# TopLevel.net
KiCad netlist of a schematic drawn in Altium Designer
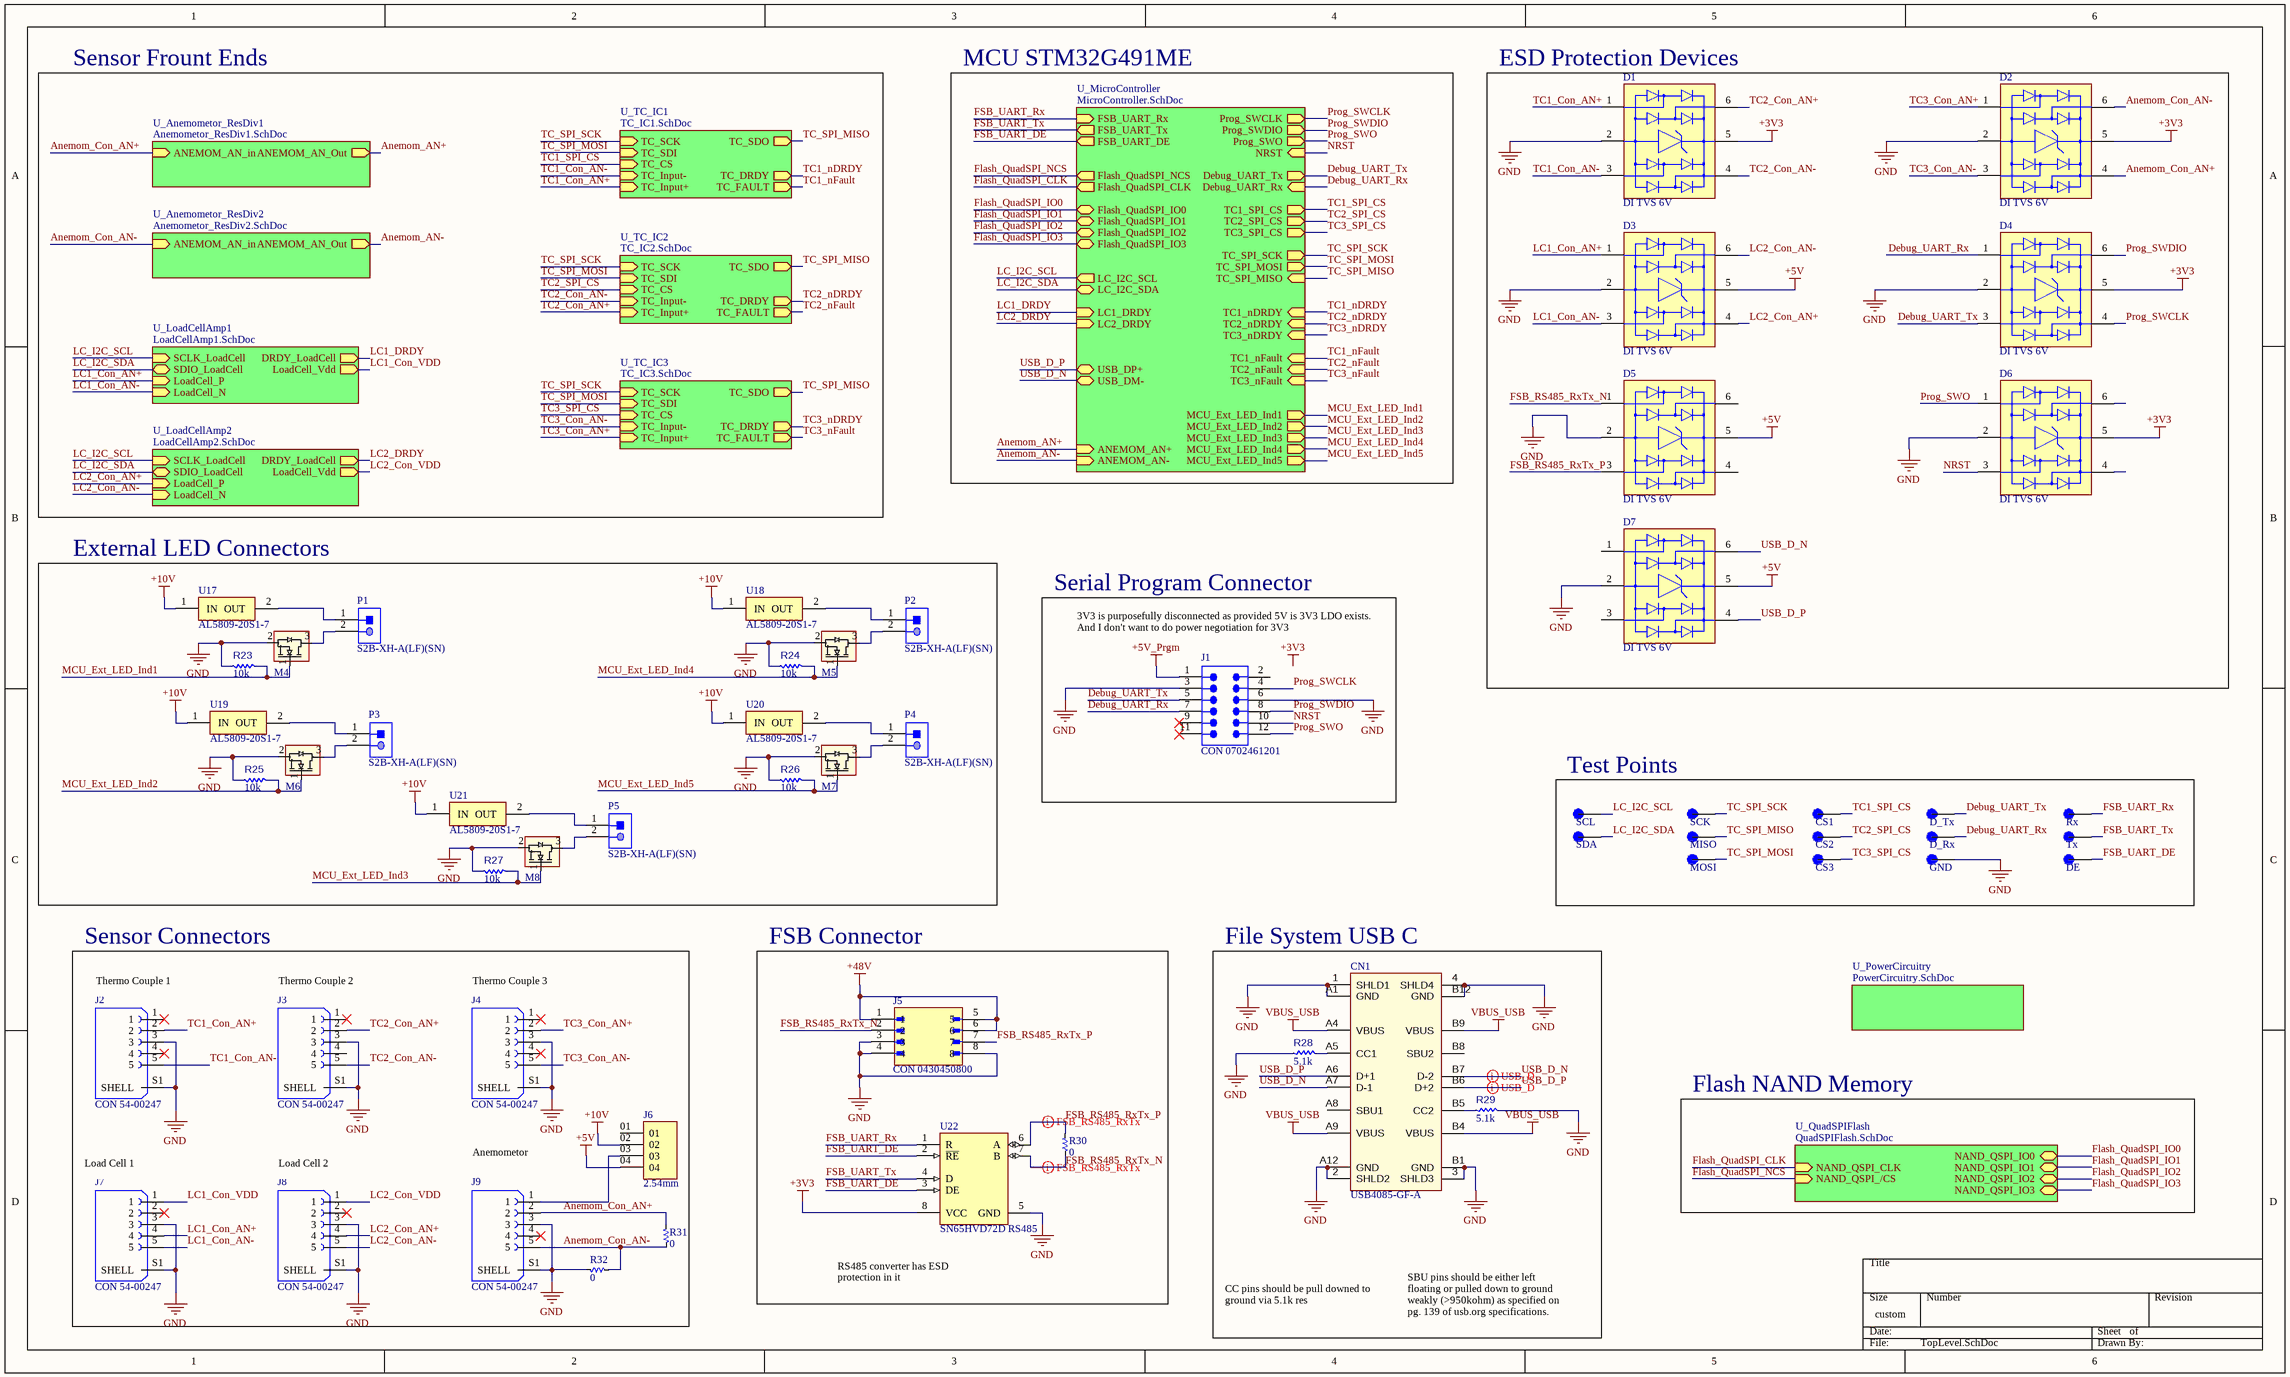
[diagram p0: TopLevel.SchDoc]

(export (version "E")
  (design (tool "Eeschema 10.0.6"))
  (components
    (comp (ref "CN1")
      (value "USB4085-GF-A")
      (footprint "FP-USB4085-GF-A-MFG")
      (description "USB Connector, 16 Contact(s), Female, Right Angle, Solder Terminal, Locking, Receptacle")
      (libsource (lib "University of Calgary - SOAR") (part "USB4085-GF-A"))
    )
    (comp (ref "CS1")
      (value "TP Clip 1206  RCWCTE")
      (footprint "1206 TP Clip RCWCTE-Footprint-1")
      (description "PC TEST POINT 1206 footprint RCWCTE")
      (libsource (lib "University of Calgary - SOAR") (part "1206"))
    )
    (comp (ref "CS2")
      (value "TP Clip 1206  RCWCTE")
      (footprint "1206 TP Clip RCWCTE-Footprint-1")
      (description "PC TEST POINT 1206 footprint RCWCTE")
      (libsource (lib "University of Calgary - SOAR") (part "1206"))
    )
    (comp (ref "CS3")
      (value "TP Clip 1206  RCWCTE")
      (footprint "1206 TP Clip RCWCTE-Footprint-1")
      (description "PC TEST POINT 1206 footprint RCWCTE")
      (libsource (lib "University of Calgary - SOAR") (part "1206"))
    )
    (comp (ref "D1")
      (value "DI TVS 6V")
      (footprint "FP-SOT363-IPC_C")
      (description "ESD Suppressors / TVS Diodes 4 Ch TVS Diode Array 3.3V 6.0A 200mW")
      (libsource (lib "University of Calgary - SOAR") (part "94170680ae7e58ce75f5909a3114e1b"))
    )
    (comp (ref "D2")
      (value "DI TVS 6V")
      (footprint "FP-SOT363-IPC_C")
      (description "ESD Suppressors / TVS Diodes 4 Ch TVS Diode Array 3.3V 6.0A 200mW")
      (libsource (lib "University of Calgary - SOAR") (part "94170680ae7e58ce75f5909a3114e1b"))
    )
    (comp (ref "D3")
      (value "DI TVS 6V")
      (footprint "FP-SOT363-IPC_C")
      (description "ESD Suppressors / TVS Diodes 4 Ch TVS Diode Array 3.3V 6.0A 200mW")
      (libsource (lib "University of Calgary - SOAR") (part "94170680ae7e58ce75f5909a3114e1b"))
    )
    (comp (ref "D4")
      (value "DI TVS 6V")
      (footprint "FP-SOT363-IPC_C")
      (description "ESD Suppressors / TVS Diodes 4 Ch TVS Diode Array 3.3V 6.0A 200mW")
      (libsource (lib "University of Calgary - SOAR") (part "94170680ae7e58ce75f5909a3114e1b"))
    )
    (comp (ref "D5")
      (value "DI TVS 6V")
      (footprint "FP-SOT363-IPC_C")
      (description "ESD Suppressors / TVS Diodes 4 Ch TVS Diode Array 3.3V 6.0A 200mW")
      (libsource (lib "University of Calgary - SOAR") (part "94170680ae7e58ce75f5909a3114e1b"))
    )
    (comp (ref "D6")
      (value "DI TVS 6V")
      (footprint "FP-SOT363-IPC_C")
      (description "ESD Suppressors / TVS Diodes 4 Ch TVS Diode Array 3.3V 6.0A 200mW")
      (libsource (lib "University of Calgary - SOAR") (part "94170680ae7e58ce75f5909a3114e1b"))
    )
    (comp (ref "D7")
      (value "DI TVS 6V")
      (footprint "FP-SOT363-IPC_C")
      (description "ESD Suppressors / TVS Diodes 4 Ch TVS Diode Array 3.3V 6.0A 200mW")
      (libsource (lib "University of Calgary - SOAR") (part "94170680ae7e58ce75f5909a3114e1b"))
    )
    (comp (ref "DE")
      (value "TP Clip 1206  RCWCTE")
      (footprint "1206 TP Clip RCWCTE-Footprint-1")
      (description "PC TEST POINT 1206 footprint RCWCTE")
      (libsource (lib "University of Calgary - SOAR") (part "1206"))
    )
    (comp (ref "D_Rx")
      (value "TP Clip 1206  RCWCTE")
      (footprint "1206 TP Clip RCWCTE-Footprint-1")
      (description "PC TEST POINT 1206 footprint RCWCTE")
      (libsource (lib "University of Calgary - SOAR") (part "1206"))
    )
    (comp (ref "D_Tx")
      (value "TP Clip 1206  RCWCTE")
      (footprint "1206 TP Clip RCWCTE-Footprint-1")
      (description "PC TEST POINT 1206 footprint RCWCTE")
      (libsource (lib "University of Calgary - SOAR") (part "1206"))
    )
    (comp (ref "GND")
      (value "TP Clip 1206  RCWCTE")
      (footprint "1206 TP Clip RCWCTE-Footprint-1")
      (description "PC TEST POINT 1206 footprint RCWCTE")
      (libsource (lib "University of Calgary - SOAR") (part "1206"))
    )
    (comp (ref "J1")
      (value "CON 0702461201")
      (footprint "FP-70246-1201-0")
      (description "Conn Shrouded Header (4 Sides) HDR 12 POS 2.54mm Solder ST Top Entry Thru-Hole C-Grid® Tray")
      (libsource (lib "University of Calgary - SOAR") (part "0702461201"))
    )
    (comp (ref "J2")
      (value "CON 54-00247")
      (footprint "CON 54-00247-Footprint-1")
      (description "Circular Connector, 5 Contact(s), Brass, Female, Solder Terminal, Socket")
      (libsource (lib "University of Calgary - SOAR") (part "54-00247-Symbol-1"))
    )
    (comp (ref "J3")
      (value "CON 54-00247")
      (footprint "CON 54-00247-Footprint-1")
      (description "Circular Connector, 5 Contact(s), Brass, Female, Solder Terminal, Socket")
      (libsource (lib "University of Calgary - SOAR") (part "54-00247-Symbol-1"))
    )
    (comp (ref "J4")
      (value "CON 54-00247")
      (footprint "CON 54-00247-Footprint-1")
      (description "Circular Connector, 5 Contact(s), Brass, Female, Solder Terminal, Socket")
      (libsource (lib "University of Calgary - SOAR") (part "54-00247-Symbol-1"))
    )
    (comp (ref "J5")
      (value "CON 0430450800")
      (footprint "CON 0430450800-Footprint-1")
      (description "0430450800 Connector Header Through Hole, Right Angle 8 position 0.118\" (3.00mm)")
      (libsource (lib "University of Calgary - SOAR") (part "0430450800"))
    )
    (comp (ref "J6")
      (value "2.54mm")
      (footprint "HEADER 4pos 2.54mm-Footprint-1")
      (description "TS-104-G-AA")
      (libsource (lib "University of Calgary - SOAR") (part "2.54mm"))
    )
    (comp (ref "J7")
      (value "CON 54-00247")
      (footprint "CON 54-00247-Footprint-1")
      (description "Circular Connector, 5 Contact(s), Brass, Female, Solder Terminal, Socket")
      (libsource (lib "University of Calgary - SOAR") (part "54-00247-Symbol-1"))
    )
    (comp (ref "J8")
      (value "CON 54-00247")
      (footprint "CON 54-00247-Footprint-1")
      (description "Circular Connector, 5 Contact(s), Brass, Female, Solder Terminal, Socket")
      (libsource (lib "University of Calgary - SOAR") (part "54-00247-Symbol-1"))
    )
    (comp (ref "J9")
      (value "CON 54-00247")
      (footprint "CON 54-00247-Footprint-1")
      (description "Circular Connector, 5 Contact(s), Brass, Female, Solder Terminal, Socket")
      (libsource (lib "University of Calgary - SOAR") (part "54-00247-Symbol-1"))
    )
    (comp (ref "M4")
      (value "MOS NMOS 30V 5.6A SOT-23")
      (footprint "PJA3404_R1_00001-Footprint-1")
      (libsource (lib "University of Calgary - SOAR") (part "TRANS-NPN-3"))
    )
    (comp (ref "M5")
      (value "MOS NMOS 30V 5.6A SOT-23")
      (footprint "PJA3404_R1_00001-Footprint-1")
      (libsource (lib "University of Calgary - SOAR") (part "TRANS-NPN-3"))
    )
    (comp (ref "M6")
      (value "MOS NMOS 30V 5.6A SOT-23")
      (footprint "PJA3404_R1_00001-Footprint-1")
      (libsource (lib "University of Calgary - SOAR") (part "TRANS-NPN-3"))
    )
    (comp (ref "M7")
      (value "MOS NMOS 30V 5.6A SOT-23")
      (footprint "PJA3404_R1_00001-Footprint-1")
      (libsource (lib "University of Calgary - SOAR") (part "TRANS-NPN-3"))
    )
    (comp (ref "M8")
      (value "MOS NMOS 30V 5.6A SOT-23")
      (footprint "PJA3404_R1_00001-Footprint-1")
      (libsource (lib "University of Calgary - SOAR") (part "TRANS-NPN-3"))
    )
    (comp (ref "MISO")
      (value "TP Clip 1206  RCWCTE")
      (footprint "1206 TP Clip RCWCTE-Footprint-1")
      (description "PC TEST POINT 1206 footprint RCWCTE")
      (libsource (lib "University of Calgary - SOAR") (part "1206"))
    )
    (comp (ref "MOSI")
      (value "TP Clip 1206  RCWCTE")
      (footprint "1206 TP Clip RCWCTE-Footprint-1")
      (description "PC TEST POINT 1206 footprint RCWCTE")
      (libsource (lib "University of Calgary - SOAR") (part "1206"))
    )
    (comp (ref "P1")
      (value "S2B-XH-A(LF)(SN)")
      (footprint "JST-S2B-XH-A(LF)(SN)_V")
      (fields (field (name "MANUFACTURER") "JST"))
      (libsource (lib "University of Calgary - SOAR") (part "CN-1P-M-R2"))
    )
    (comp (ref "P2")
      (value "S2B-XH-A(LF)(SN)")
      (footprint "JST-S2B-XH-A(LF)(SN)_V")
      (fields (field (name "MANUFACTURER") "JST"))
      (libsource (lib "University of Calgary - SOAR") (part "CN-1P-M-R2"))
    )
    (comp (ref "P3")
      (value "S2B-XH-A(LF)(SN)")
      (footprint "JST-S2B-XH-A(LF)(SN)_V")
      (fields (field (name "MANUFACTURER") "JST"))
      (libsource (lib "University of Calgary - SOAR") (part "CN-1P-M-R2"))
    )
    (comp (ref "P4")
      (value "S2B-XH-A(LF)(SN)")
      (footprint "JST-S2B-XH-A(LF)(SN)_V")
      (fields (field (name "MANUFACTURER") "JST"))
      (libsource (lib "University of Calgary - SOAR") (part "CN-1P-M-R2"))
    )
    (comp (ref "P5")
      (value "S2B-XH-A(LF)(SN)")
      (footprint "JST-S2B-XH-A(LF)(SN)_V")
      (fields (field (name "MANUFACTURER") "JST"))
      (libsource (lib "University of Calgary - SOAR") (part "CN-1P-M-R2"))
    )
    (comp (ref "R23")
      (value "10k")
      (footprint "RESC2013X50X35ML15T15")
      (description "Chip Resistor, 10 KOhm, +/- 1%, 125 mW, -55 to 155 degC, 0805 (2012 Metric)")
      (fields (field (name "POWER") "125mW") (field (name "TOLERANCE") "1%"))
      (libsource (lib "University of Calgary - SOAR") (part "RES-2"))
    )
    (comp (ref "R24")
      (value "10k")
      (footprint "RESC2013X50X35ML15T15")
      (description "Chip Resistor, 10 KOhm, +/- 1%, 125 mW, -55 to 155 degC, 0805 (2012 Metric)")
      (fields (field (name "POWER") "125mW") (field (name "TOLERANCE") "1%"))
      (libsource (lib "University of Calgary - SOAR") (part "RES-2"))
    )
    (comp (ref "R25")
      (value "10k")
      (footprint "RESC2013X50X35ML15T15")
      (description "Chip Resistor, 10 KOhm, +/- 1%, 125 mW, -55 to 155 degC, 0805 (2012 Metric)")
      (fields (field (name "POWER") "125mW") (field (name "TOLERANCE") "1%"))
      (libsource (lib "University of Calgary - SOAR") (part "RES-2"))
    )
    (comp (ref "R26")
      (value "10k")
      (footprint "RESC2013X50X35ML15T15")
      (description "Chip Resistor, 10 KOhm, +/- 1%, 125 mW, -55 to 155 degC, 0805 (2012 Metric)")
      (fields (field (name "POWER") "125mW") (field (name "TOLERANCE") "1%"))
      (libsource (lib "University of Calgary - SOAR") (part "RES-2"))
    )
    (comp (ref "R27")
      (value "10k")
      (footprint "RESC2013X50X35ML15T15")
      (description "Chip Resistor, 10 KOhm, +/- 1%, 125 mW, -55 to 155 degC, 0805 (2012 Metric)")
      (fields (field (name "POWER") "125mW") (field (name "TOLERANCE") "1%"))
      (libsource (lib "University of Calgary - SOAR") (part "RES-2"))
    )
    (comp (ref "R28")
      (value "5.1k")
      (footprint "RESC1608X55X25ML10T15")
      (fields
        (field (name "POWER") "100mW")
        (field (name "TOLERANCE") "1%")
        (field (name "Comment") "RC0603FR-075K1L")
      )
      (libsource (lib "University of Calgary - SOAR") (part "RES-2"))
    )
    (comp (ref "R29")
      (value "5.1k")
      (footprint "RESC1608X55X25ML10T15")
      (fields
        (field (name "POWER") "100mW")
        (field (name "TOLERANCE") "1%")
        (field (name "Comment") "RC0603FR-075K1L")
      )
      (libsource (lib "University of Calgary - SOAR") (part "RES-2"))
    )
    (comp (ref "R30")
      (value "0")
      (footprint "0603")
      (description "0 Ohms Jumper 0.1W, 1/10W Chip Resistor 0603 (1608 Metric) Automotive AEC-Q200 Thick Film")
      (fields
        (field (name "MANUFACTURER PART #") "RMCF0603ZT0R00")
        (field (name "MANUFACTURER") "Stackpole Electronics Inc")
        (field (name "SOURCE") "PlumBay_SchLib.SchLib")
      )
      (libsource (lib "University of Calgary - SOAR") (part "RT-0R00-F-1/10W-0603"))
    )
    (comp (ref "R31")
      (value "0")
      (footprint "0603")
      (description "0 Ohms Jumper 0.1W, 1/10W Chip Resistor 0603 (1608 Metric) Automotive AEC-Q200 Thick Film")
      (fields
        (field (name "MANUFACTURER PART #") "RMCF0603ZT0R00")
        (field (name "MANUFACTURER") "Stackpole Electronics Inc")
        (field (name "SOURCE") "PlumBay_SchLib.SchLib")
      )
      (libsource (lib "University of Calgary - SOAR") (part "RT-0R00-F-1/10W-0603"))
    )
    (comp (ref "R32")
      (value "0")
      (footprint "0603")
      (description "0 Ohms Jumper 0.1W, 1/10W Chip Resistor 0603 (1608 Metric) Automotive AEC-Q200 Thick Film")
      (fields
        (field (name "MANUFACTURER PART #") "RMCF0603ZT0R00")
        (field (name "MANUFACTURER") "Stackpole Electronics Inc")
        (field (name "SOURCE") "PlumBay_SchLib.SchLib")
      )
      (libsource (lib "University of Calgary - SOAR") (part "RT-0R00-F-1/10W-0603"))
    )
    (comp (ref "Rx")
      (value "TP Clip 1206  RCWCTE")
      (footprint "1206 TP Clip RCWCTE-Footprint-1")
      (description "PC TEST POINT 1206 footprint RCWCTE")
      (libsource (lib "University of Calgary - SOAR") (part "1206"))
    )
    (comp (ref "SCK")
      (value "TP Clip 1206  RCWCTE")
      (footprint "1206 TP Clip RCWCTE-Footprint-1")
      (description "PC TEST POINT 1206 footprint RCWCTE")
      (libsource (lib "University of Calgary - SOAR") (part "1206"))
    )
    (comp (ref "SCL")
      (value "TP Clip 1206  RCWCTE")
      (footprint "1206 TP Clip RCWCTE-Footprint-1")
      (description "PC TEST POINT 1206 footprint RCWCTE")
      (libsource (lib "University of Calgary - SOAR") (part "1206"))
    )
    (comp (ref "SDA")
      (value "TP Clip 1206  RCWCTE")
      (footprint "1206 TP Clip RCWCTE-Footprint-1")
      (description "PC TEST POINT 1206 footprint RCWCTE")
      (libsource (lib "University of Calgary - SOAR") (part "1206"))
    )
    (comp (ref "Tx")
      (value "TP Clip 1206  RCWCTE")
      (footprint "1206 TP Clip RCWCTE-Footprint-1")
      (description "PC TEST POINT 1206 footprint RCWCTE")
      (libsource (lib "University of Calgary - SOAR") (part "1206"))
    )
    (comp (ref "U17")
      (value "AL5809-20S1-7")
      (footprint "DIOD-SOD123-A_V")
      (description "Led Driver, Cc/Linear, -40 To 125Deg C Rohs Compliant: Yes")
      (libsource (lib "University of Calgary - SOAR") (part "DIOD-AL5809-2"))
    )
    (comp (ref "U18")
      (value "AL5809-20S1-7")
      (footprint "DIOD-SOD123-A_V")
      (description "Led Driver, Cc/Linear, -40 To 125Deg C Rohs Compliant: Yes")
      (libsource (lib "University of Calgary - SOAR") (part "DIOD-AL5809-2"))
    )
    (comp (ref "U19")
      (value "AL5809-20S1-7")
      (footprint "DIOD-SOD123-A_V")
      (description "Led Driver, Cc/Linear, -40 To 125Deg C Rohs Compliant: Yes")
      (libsource (lib "University of Calgary - SOAR") (part "DIOD-AL5809-2"))
    )
    (comp (ref "U20")
      (value "AL5809-20S1-7")
      (footprint "DIOD-SOD123-A_V")
      (description "Led Driver, Cc/Linear, -40 To 125Deg C Rohs Compliant: Yes")
      (libsource (lib "University of Calgary - SOAR") (part "DIOD-AL5809-2"))
    )
    (comp (ref "U21")
      (value "AL5809-20S1-7")
      (footprint "DIOD-SOD123-A_V")
      (description "Led Driver, Cc/Linear, -40 To 125Deg C Rohs Compliant: Yes")
      (libsource (lib "University of Calgary - SOAR") (part "DIOD-AL5809-2"))
    )
    (comp (ref "U22")
      (value "SN65HVD72D RS485")
      (footprint "D0008A_L")
      (description "Line Transceiver, 1 Func, 1 Driver, 1 Rcvr, PDSO8")
      (libsource (lib "University of Calgary - SOAR") (part "TI-SN65HVD7X-SOIC_D-8"))
    )
  )
  (nets
    (net (code "1") (name "+3V3") (class "Default")
      (node (ref "D1") (pin "5") (pinfunction "VP_5") (pintype "passive"))
      (node (ref "D2") (pin "5") (pinfunction "VP_5") (pintype "passive"))
      (node (ref "D4") (pin "5") (pinfunction "VP_5") (pintype "passive"))
      (node (ref "D6") (pin "5") (pinfunction "VP_5") (pintype "passive"))
      (node (ref "U22") (pin "8") (pinfunction "VCC_8") (pintype "power_in"))
    )
    (net (code "2") (name "+5V") (class "Default")
      (node (ref "D3") (pin "5") (pinfunction "VP_5") (pintype "passive"))
      (node (ref "D5") (pin "5") (pinfunction "VP_5") (pintype "passive"))
      (node (ref "D7") (pin "5") (pinfunction "VP_5") (pintype "passive"))
      (node (ref "J6") (pin "04") (pinfunction "04_04") (pintype "passive"))
    )
    (net (code "3") (name "+5V_Prgm") (class "Default")
      (node (ref "J1") (pin "1") (pinfunction "1_1") (pintype "passive"))
    )
    (net (code "4") (name "+10V") (class "Default")
      (node (ref "J6") (pin "02") (pinfunction "02_02") (pintype "passive"))
      (node (ref "U17") (pin "1") (pinfunction "IN_1") (pintype "passive"))
      (node (ref "U18") (pin "1") (pinfunction "IN_1") (pintype "passive"))
      (node (ref "U19") (pin "1") (pinfunction "IN_1") (pintype "passive"))
      (node (ref "U20") (pin "1") (pinfunction "IN_1") (pintype "passive"))
      (node (ref "U21") (pin "1") (pinfunction "IN_1") (pintype "passive"))
    )
    (net (code "5") (name "+48V") (class "Default")
      (node (ref "J5") (pin "1") (pinfunction "1_1") (pintype "passive"))
      (node (ref "J5") (pin "5") (pinfunction "5_5") (pintype "passive"))
      (node (ref "J5") (pin "6") (pinfunction "6_6") (pintype "passive"))
    )
    (net (code "8") (name "/Anemom_Con_AN+") (class "Default")
      (node (ref "D2") (pin "4") (pinfunction "CH3_4") (pintype "passive"))
      (node (ref "J9") (pin "2") (pinfunction "2_2") (pintype "passive"))
      (node (ref "R31") (pin "2") (pintype "passive"))
    )
    (net (code "9") (name "/Anemom_Con_AN-") (class "Default")
      (node (ref "D2") (pin "6") (pinfunction "CH4_6") (pintype "passive"))
      (node (ref "J9") (pin "5") (pinfunction "5_5") (pintype "passive"))
      (node (ref "R31") (pin "1") (pintype "passive"))
      (node (ref "R32") (pin "2") (pintype "passive"))
    )
    (net (code "10") (name "/Debug_UART_Rx") (class "Default")
      (node (ref "D4") (pin "1") (pinfunction "CH1_1") (pintype "passive"))
      (node (ref "D_Rx") (pin "1") (pinfunction "TP_1") (pintype "passive"))
      (node (ref "J1") (pin "7") (pinfunction "7_7") (pintype "passive"))
    )
    (net (code "11") (name "/Debug_UART_Tx") (class "Default")
      (node (ref "D4") (pin "3") (pinfunction "CH2_3") (pintype "passive"))
      (node (ref "D_Tx") (pin "1") (pinfunction "TP_1") (pintype "passive"))
      (node (ref "J1") (pin "5") (pinfunction "5_5") (pintype "passive"))
    )
    (net (code "12") (name "/FSB_RS485_RxTx_N") (class "Default")
      (node (ref "D5") (pin "1") (pinfunction "CH1_1") (pintype "passive"))
      (node (ref "J5") (pin "2") (pinfunction "2_2") (pintype "passive"))
      (node (ref "R30") (pin "1") (pintype "passive"))
      (node (ref "U22") (pin "7") (pinfunction "B_7") (pintype "bidirectional"))
    )
    (net (code "13") (name "/FSB_RS485_RxTx_P") (class "Default")
      (node (ref "D5") (pin "3") (pinfunction "CH2_3") (pintype "passive"))
      (node (ref "J5") (pin "7") (pinfunction "7_7") (pintype "passive"))
      (node (ref "R30") (pin "2") (pintype "passive"))
      (node (ref "U22") (pin "6") (pinfunction "A_6") (pintype "bidirectional"))
    )
    (net (code "14") (name "/FSB_UART_DE") (class "Default")
      (node (ref "DE") (pin "1") (pinfunction "TP_1") (pintype "passive"))
      (node (ref "U22") (pin "2") (pinfunction "~{RE}_2") (pintype "input"))
      (node (ref "U22") (pin "3") (pinfunction "DE_3") (pintype "input"))
    )
    (net (code "15") (name "/FSB_UART_Rx") (class "Default")
      (node (ref "Rx") (pin "1") (pinfunction "TP_1") (pintype "passive"))
      (node (ref "U22") (pin "1") (pinfunction "R_1") (pintype "tri_state"))
    )
    (net (code "16") (name "/FSB_UART_Tx") (class "Default")
      (node (ref "Tx") (pin "1") (pinfunction "TP_1") (pintype "passive"))
      (node (ref "U22") (pin "4") (pinfunction "D_4") (pintype "input"))
    )
    (net (code "23") (name "/LC1_Con_AN+") (class "Default")
      (node (ref "D3") (pin "1") (pinfunction "CH1_1") (pintype "passive"))
      (node (ref "J7") (pin "4") (pinfunction "4_4") (pintype "passive"))
    )
    (net (code "24") (name "/LC1_Con_AN-") (class "Default")
      (node (ref "D3") (pin "3") (pinfunction "CH2_3") (pintype "passive"))
      (node (ref "J7") (pin "5") (pinfunction "5_5") (pintype "passive"))
    )
    (net (code "25") (name "/LC1_Con_VDD") (class "Default")
      (node (ref "J7") (pin "1") (pinfunction "1_1") (pintype "passive"))
    )
    (net (code "27") (name "/LC2_Con_AN+") (class "Default")
      (node (ref "D3") (pin "4") (pinfunction "CH3_4") (pintype "passive"))
      (node (ref "J8") (pin "4") (pinfunction "4_4") (pintype "passive"))
    )
    (net (code "28") (name "/LC2_Con_AN-") (class "Default")
      (node (ref "D3") (pin "6") (pinfunction "CH4_6") (pintype "passive"))
      (node (ref "J8") (pin "5") (pinfunction "5_5") (pintype "passive"))
    )
    (net (code "29") (name "/LC2_Con_VDD") (class "Default")
      (node (ref "J8") (pin "1") (pinfunction "1_1") (pintype "passive"))
    )
    (net (code "31") (name "/LC_I2C_SCL") (class "Default")
      (node (ref "SCL") (pin "1") (pinfunction "TP_1") (pintype "passive"))
    )
    (net (code "32") (name "/LC_I2C_SDA") (class "Default")
      (node (ref "SDA") (pin "1") (pinfunction "TP_1") (pintype "passive"))
    )
    (net (code "33") (name "/MCU_Ext_LED_Ind1") (class "Default")
      (node (ref "M4") (pin "1") (pinfunction "1_1") (pintype "passive"))
      (node (ref "R23") (pin "1") (pinfunction "1_1") (pintype "passive"))
    )
    (net (code "34") (name "/MCU_Ext_LED_Ind2") (class "Default")
      (node (ref "M6") (pin "1") (pinfunction "1_1") (pintype "passive"))
      (node (ref "R25") (pin "1") (pinfunction "1_1") (pintype "passive"))
    )
    (net (code "35") (name "/MCU_Ext_LED_Ind3") (class "Default")
      (node (ref "M8") (pin "1") (pinfunction "1_1") (pintype "passive"))
      (node (ref "R27") (pin "1") (pinfunction "1_1") (pintype "passive"))
    )
    (net (code "36") (name "/MCU_Ext_LED_Ind4") (class "Default")
      (node (ref "M5") (pin "1") (pinfunction "1_1") (pintype "passive"))
      (node (ref "R24") (pin "1") (pinfunction "1_1") (pintype "passive"))
    )
    (net (code "37") (name "/MCU_Ext_LED_Ind5") (class "Default")
      (node (ref "M7") (pin "1") (pinfunction "1_1") (pintype "passive"))
      (node (ref "R26") (pin "1") (pinfunction "1_1") (pintype "passive"))
    )
    (net (code "38") (name "/NRST") (class "Default")
      (node (ref "D6") (pin "3") (pinfunction "CH2_3") (pintype "passive"))
      (node (ref "J1") (pin "10") (pinfunction "10_10") (pintype "passive"))
    )
    (net (code "39") (name "/Prog_SWCLK") (class "Default")
      (node (ref "D4") (pin "4") (pinfunction "CH3_4") (pintype "passive"))
      (node (ref "J1") (pin "4") (pinfunction "4_4") (pintype "passive"))
    )
    (net (code "40") (name "/Prog_SWDIO") (class "Default")
      (node (ref "D4") (pin "6") (pinfunction "CH4_6") (pintype "passive"))
      (node (ref "J1") (pin "8") (pinfunction "8_8") (pintype "passive"))
    )
    (net (code "41") (name "/Prog_SWO") (class "Default")
      (node (ref "D6") (pin "1") (pinfunction "CH1_1") (pintype "passive"))
      (node (ref "J1") (pin "12") (pinfunction "12_12") (pintype "passive"))
    )
    (net (code "42") (name "/TC1_Con_AN+") (class "Default")
      (node (ref "D1") (pin "1") (pinfunction "CH1_1") (pintype "passive"))
      (node (ref "J2") (pin "2") (pinfunction "2_2") (pintype "passive"))
    )
    (net (code "43") (name "/TC1_Con_AN-") (class "Default")
      (node (ref "D1") (pin "3") (pinfunction "CH2_3") (pintype "passive"))
      (node (ref "J2") (pin "5") (pinfunction "5_5") (pintype "passive"))
    )
    (net (code "44") (name "/TC1_SPI_CS") (class "Default")
      (node (ref "CS1") (pin "1") (pinfunction "TP_1") (pintype "passive"))
    )
    (net (code "47") (name "/TC2_Con_AN+") (class "Default")
      (node (ref "D1") (pin "6") (pinfunction "CH4_6") (pintype "passive"))
      (node (ref "J3") (pin "2") (pinfunction "2_2") (pintype "passive"))
    )
    (net (code "48") (name "/TC2_Con_AN-") (class "Default")
      (node (ref "D1") (pin "4") (pinfunction "CH3_4") (pintype "passive"))
      (node (ref "J3") (pin "5") (pinfunction "5_5") (pintype "passive"))
    )
    (net (code "49") (name "/TC2_SPI_CS") (class "Default")
      (node (ref "CS2") (pin "1") (pinfunction "TP_1") (pintype "passive"))
    )
    (net (code "52") (name "/TC3_Con_AN+") (class "Default")
      (node (ref "D2") (pin "1") (pinfunction "CH1_1") (pintype "passive"))
      (node (ref "J4") (pin "2") (pinfunction "2_2") (pintype "passive"))
    )
    (net (code "53") (name "/TC3_Con_AN-") (class "Default")
      (node (ref "D2") (pin "3") (pinfunction "CH2_3") (pintype "passive"))
      (node (ref "J4") (pin "5") (pinfunction "5_5") (pintype "passive"))
    )
    (net (code "54") (name "/TC3_SPI_CS") (class "Default")
      (node (ref "CS3") (pin "1") (pinfunction "TP_1") (pintype "passive"))
    )
    (net (code "57") (name "/TC_SPI_MISO") (class "Default")
      (node (ref "MISO") (pin "1") (pinfunction "TP_1") (pintype "passive"))
    )
    (net (code "58") (name "/TC_SPI_MOSI") (class "Default")
      (node (ref "MOSI") (pin "1") (pinfunction "TP_1") (pintype "passive"))
    )
    (net (code "59") (name "/TC_SPI_SCK") (class "Default")
      (node (ref "SCK") (pin "1") (pinfunction "TP_1") (pintype "passive"))
    )
    (net (code "60") (name "/USB_D_N") (class "Default")
      (node (ref "CN1") (pin "A7") (pinfunction "D-1_A7") (pintype "passive"))
      (node (ref "CN1") (pin "B7") (pinfunction "D-2_B7") (pintype "passive"))
      (node (ref "D7") (pin "6") (pinfunction "CH4_6") (pintype "passive"))
    )
    (net (code "61") (name "/USB_D_P") (class "Default")
      (node (ref "CN1") (pin "A6") (pinfunction "D+1_A6") (pintype "passive"))
      (node (ref "CN1") (pin "B6") (pinfunction "D+2_B6") (pintype "passive"))
      (node (ref "D7") (pin "4") (pinfunction "CH3_4") (pintype "passive"))
    )
    (net (code "62") (name "GND") (class "Default")
      (node (ref "CN1") (pin "1") (pinfunction "SHLD1_1") (pintype "passive"))
      (node (ref "CN1") (pin "2") (pinfunction "SHLD2_2") (pintype "passive"))
      (node (ref "CN1") (pin "3") (pinfunction "SHLD3_3") (pintype "passive"))
      (node (ref "CN1") (pin "4") (pinfunction "SHLD4_4") (pintype "passive"))
      (node (ref "CN1") (pin "A1") (pinfunction "GND_A1") (pintype "passive"))
      (node (ref "CN1") (pin "A12") (pinfunction "GND_A12") (pintype "passive"))
      (node (ref "CN1") (pin "B1") (pinfunction "GND_B1") (pintype "passive"))
      (node (ref "CN1") (pin "B12") (pinfunction "GND_B12") (pintype "passive"))
      (node (ref "D1") (pin "2") (pinfunction "VN_2") (pintype "passive"))
      (node (ref "D2") (pin "2") (pinfunction "VN_2") (pintype "passive"))
      (node (ref "D3") (pin "2") (pinfunction "VN_2") (pintype "passive"))
      (node (ref "D4") (pin "2") (pinfunction "VN_2") (pintype "passive"))
      (node (ref "D5") (pin "2") (pinfunction "VN_2") (pintype "passive"))
      (node (ref "D6") (pin "2") (pinfunction "VN_2") (pintype "passive"))
      (node (ref "D7") (pin "2") (pinfunction "VN_2") (pintype "passive"))
      (node (ref "GND") (pin "1") (pinfunction "TP_1") (pintype "passive"))
      (node (ref "J1") (pin "3") (pinfunction "3_3") (pintype "passive"))
      (node (ref "J1") (pin "6") (pinfunction "6_6") (pintype "passive"))
      (node (ref "J2") (pin "3") (pinfunction "3_3") (pintype "passive"))
      (node (ref "J2") (pin "S1") (pinfunction "SHELL_S1") (pintype "passive"))
      (node (ref "J3") (pin "3") (pinfunction "3_3") (pintype "passive"))
      (node (ref "J3") (pin "S1") (pinfunction "SHELL_S1") (pintype "passive"))
      (node (ref "J4") (pin "3") (pinfunction "3_3") (pintype "passive"))
      (node (ref "J4") (pin "S1") (pinfunction "SHELL_S1") (pintype "passive"))
      (node (ref "J5") (pin "3") (pinfunction "3_3") (pintype "passive"))
      (node (ref "J5") (pin "4") (pinfunction "4_4") (pintype "passive"))
      (node (ref "J5") (pin "8") (pinfunction "8_8") (pintype "passive"))
      (node (ref "J7") (pin "3") (pinfunction "3_3") (pintype "passive"))
      (node (ref "J7") (pin "S1") (pinfunction "SHELL_S1") (pintype "passive"))
      (node (ref "J8") (pin "3") (pinfunction "3_3") (pintype "passive"))
      (node (ref "J8") (pin "S1") (pinfunction "SHELL_S1") (pintype "passive"))
      (node (ref "J9") (pin "3") (pinfunction "3_3") (pintype "passive"))
      (node (ref "J9") (pin "S1") (pinfunction "SHELL_S1") (pintype "passive"))
      (node (ref "M4") (pin "2") (pinfunction "2_2") (pintype "passive"))
      (node (ref "M5") (pin "2") (pinfunction "2_2") (pintype "passive"))
      (node (ref "M6") (pin "2") (pinfunction "2_2") (pintype "passive"))
      (node (ref "M7") (pin "2") (pinfunction "2_2") (pintype "passive"))
      (node (ref "M8") (pin "2") (pinfunction "2_2") (pintype "passive"))
      (node (ref "R23") (pin "2") (pinfunction "2_2") (pintype "passive"))
      (node (ref "R24") (pin "2") (pinfunction "2_2") (pintype "passive"))
      (node (ref "R25") (pin "2") (pinfunction "2_2") (pintype "passive"))
      (node (ref "R26") (pin "2") (pinfunction "2_2") (pintype "passive"))
      (node (ref "R27") (pin "2") (pinfunction "2_2") (pintype "passive"))
      (node (ref "R28") (pin "1") (pinfunction "1_1") (pintype "passive"))
      (node (ref "R29") (pin "2") (pinfunction "2_2") (pintype "passive"))
      (node (ref "R32") (pin "1") (pintype "passive"))
      (node (ref "U22") (pin "5") (pinfunction "GND_5") (pintype "power_in"))
    )
    (net (code "63") (name "Net-(CN1-CC1)") (class "Default")
      (node (ref "CN1") (pin "A5") (pinfunction "CC1_A5") (pintype "passive"))
      (node (ref "R28") (pin "2") (pinfunction "2_2") (pintype "passive"))
    )
    (net (code "64") (name "Net-(CN1-CC2)") (class "Default")
      (node (ref "CN1") (pin "B5") (pinfunction "CC2_B5") (pintype "passive"))
      (node (ref "R29") (pin "1") (pinfunction "1_1") (pintype "passive"))
    )
    (net (code "65") (name "Net-(J6-Pad03)") (class "Default")
      (node (ref "J6") (pin "03") (pinfunction "03_03") (pintype "passive"))
      (node (ref "J9") (pin "1") (pinfunction "1_1") (pintype "passive"))
    )
    (net (code "66") (name "Net-(M4-Pad3)") (class "Default")
      (node (ref "M4") (pin "3") (pinfunction "3_3") (pintype "passive"))
      (node (ref "P1") (pin "2") (pinfunction "2_2") (pintype "passive"))
    )
    (net (code "67") (name "Net-(M5-Pad3)") (class "Default")
      (node (ref "M5") (pin "3") (pinfunction "3_3") (pintype "passive"))
      (node (ref "P2") (pin "2") (pinfunction "2_2") (pintype "passive"))
    )
    (net (code "68") (name "Net-(M6-Pad3)") (class "Default")
      (node (ref "M6") (pin "3") (pinfunction "3_3") (pintype "passive"))
      (node (ref "P3") (pin "2") (pinfunction "2_2") (pintype "passive"))
    )
    (net (code "69") (name "Net-(M7-Pad3)") (class "Default")
      (node (ref "M7") (pin "3") (pinfunction "3_3") (pintype "passive"))
      (node (ref "P4") (pin "2") (pinfunction "2_2") (pintype "passive"))
    )
    (net (code "70") (name "Net-(M8-Pad3)") (class "Default")
      (node (ref "M8") (pin "3") (pinfunction "3_3") (pintype "passive"))
      (node (ref "P5") (pin "2") (pinfunction "2_2") (pintype "passive"))
    )
    (net (code "71") (name "Net-(U17-OUT)") (class "Default")
      (node (ref "P1") (pin "1") (pinfunction "1_1") (pintype "passive"))
      (node (ref "U17") (pin "2") (pinfunction "OUT_2") (pintype "passive"))
    )
    (net (code "72") (name "Net-(U18-OUT)") (class "Default")
      (node (ref "P2") (pin "1") (pinfunction "1_1") (pintype "passive"))
      (node (ref "U18") (pin "2") (pinfunction "OUT_2") (pintype "passive"))
    )
    (net (code "73") (name "Net-(U19-OUT)") (class "Default")
      (node (ref "P3") (pin "1") (pinfunction "1_1") (pintype "passive"))
      (node (ref "U19") (pin "2") (pinfunction "OUT_2") (pintype "passive"))
    )
    (net (code "74") (name "Net-(U20-OUT)") (class "Default")
      (node (ref "P4") (pin "1") (pinfunction "1_1") (pintype "passive"))
      (node (ref "U20") (pin "2") (pinfunction "OUT_2") (pintype "passive"))
    )
    (net (code "75") (name "Net-(U21-OUT)") (class "Default")
      (node (ref "P5") (pin "1") (pinfunction "1_1") (pintype "passive"))
      (node (ref "U21") (pin "2") (pinfunction "OUT_2") (pintype "passive"))
    )
    (net (code "76") (name "VBUS_USB") (class "Default")
      (node (ref "CN1") (pin "A4") (pinfunction "VBUS_A4") (pintype "passive"))
      (node (ref "CN1") (pin "A9") (pinfunction "VBUS_A9") (pintype "passive"))
      (node (ref "CN1") (pin "B4") (pinfunction "VBUS_B4") (pintype "passive"))
      (node (ref "CN1") (pin "B9") (pinfunction "VBUS_B9") (pintype "passive"))
    )
    (net (code "77") (name "unconnected-(CN1-SBU1-PadA8)") (class "Default")
      (node (ref "CN1") (pin "A8") (pinfunction "SBU1_A8") (pintype "passive"))
    )
    (net (code "78") (name "unconnected-(CN1-SBU2-PadB8)") (class "Default")
      (node (ref "CN1") (pin "B8") (pinfunction "SBU2_B8") (pintype "passive"))
    )
    (net (code "79") (name "unconnected-(D5-CH3-Pad4)") (class "Default")
      (node (ref "D5") (pin "4") (pinfunction "CH3_4") (pintype "passive"))
    )
    (net (code "80") (name "unconnected-(D5-CH4-Pad6)") (class "Default")
      (node (ref "D5") (pin "6") (pinfunction "CH4_6") (pintype "passive"))
    )
    (net (code "81") (name "unconnected-(D6-CH3-Pad4)") (class "Default")
      (node (ref "D6") (pin "4") (pinfunction "CH3_4") (pintype "passive"))
    )
    (net (code "82") (name "unconnected-(D6-CH4-Pad6)") (class "Default")
      (node (ref "D6") (pin "6") (pinfunction "CH4_6") (pintype "passive"))
    )
    (net (code "83") (name "unconnected-(D7-CH1-Pad1)") (class "Default")
      (node (ref "D7") (pin "1") (pinfunction "CH1_1") (pintype "passive"))
    )
    (net (code "84") (name "unconnected-(D7-CH2-Pad3)") (class "Default")
      (node (ref "D7") (pin "3") (pinfunction "CH2_3") (pintype "passive"))
    )
    (net (code "85") (name "unconnected-(J1-Pad2)") (class "Default")
      (node (ref "J1") (pin "2") (pinfunction "2_2") (pintype "passive"))
    )
    (net (code "86") (name "unconnected-(J1-Pad9)") (class "Default")
      (node (ref "J1") (pin "9") (pinfunction "9_9") (pintype "passive+no_connect"))
    )
    (net (code "87") (name "unconnected-(J1-Pad11)") (class "Default")
      (node (ref "J1") (pin "11") (pinfunction "11_11") (pintype "passive+no_connect"))
    )
    (net (code "88") (name "unconnected-(J2-Pad1)") (class "Default")
      (node (ref "J2") (pin "1") (pinfunction "1_1") (pintype "passive+no_connect"))
    )
    (net (code "89") (name "unconnected-(J2-Pad4)") (class "Default")
      (node (ref "J2") (pin "4") (pinfunction "4_4") (pintype "passive+no_connect"))
    )
    (net (code "90") (name "unconnected-(J3-Pad1)") (class "Default")
      (node (ref "J3") (pin "1") (pinfunction "1_1") (pintype "passive+no_connect"))
    )
    (net (code "91") (name "unconnected-(J3-Pad4)") (class "Default")
      (node (ref "J3") (pin "4") (pinfunction "4_4") (pintype "passive"))
    )
    (net (code "92") (name "unconnected-(J4-Pad1)") (class "Default")
      (node (ref "J4") (pin "1") (pinfunction "1_1") (pintype "passive+no_connect"))
    )
    (net (code "93") (name "unconnected-(J4-Pad4)") (class "Default")
      (node (ref "J4") (pin "4") (pinfunction "4_4") (pintype "passive+no_connect"))
    )
    (net (code "94") (name "unconnected-(J6-Pad01)") (class "Default")
      (node (ref "J6") (pin "01") (pinfunction "01_01") (pintype "passive"))
    )
    (net (code "95") (name "unconnected-(J7-Pad2)") (class "Default")
      (node (ref "J7") (pin "2") (pinfunction "2_2") (pintype "passive+no_connect"))
    )
    (net (code "96") (name "unconnected-(J8-Pad2)") (class "Default")
      (node (ref "J8") (pin "2") (pinfunction "2_2") (pintype "passive+no_connect"))
    )
    (net (code "97") (name "unconnected-(J9-Pad4)") (class "Default")
      (node (ref "J9") (pin "4") (pinfunction "4_4") (pintype "passive+no_connect"))
    )
  )
)
